# DigitalInput.net
KiCad netlist of a schematic drawn in EAGLE
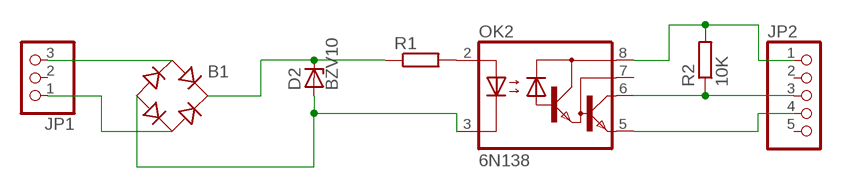
[diagram p0: schematic, sheet 1]

(export (version "E")
  (design (tool "Eeschema 10.0.6"))
  (components
    (comp (ref "B1")
      (value "B-DIL")
      (footprint "eagle-import:B-DIL")
      (libsource (lib "eagle-import") (part "B-DIL"))
    )
    (comp (ref "D2")
      (value "BZV10")
      (footprint "eagle-import:DO34Z7")
      (libsource (lib "eagle-import") (part "BZV10"))
    )
    (comp (ref "JP1")
      (value "PINHD-1X3")
      (footprint "eagle-import:1X03")
      (libsource (lib "eagle-import") (part "PINHD-1X3"))
    )
    (comp (ref "JP2")
      (value "PINHD-1X5")
      (footprint "eagle-import:1X05")
      (libsource (lib "eagle-import") (part "PINHD-1X5"))
    )
    (comp (ref "OK2")
      (value "6N138")
      (footprint "eagle-import:DIL08")
      (fields (field (name "MF") "VISHAY/TELEFUNKEN"))
      (libsource (lib "eagle-import") (part "6N138"))
    )
    (comp (ref "R1")
      (value "R-EU_0204/7")
      (footprint "eagle-import:0204_7")
      (libsource (lib "eagle-import") (part "R-EU_0204/7"))
    )
    (comp (ref "R2")
      (value "10K")
      (footprint "eagle-import:0207_5V")
      (libsource (lib "eagle-import") (part "R-EU_0207/5V"))
    )
  )
  (nets
    (net (code "1") (name "Net-(B1-Pad+)") (class "Default")
      (node (ref "B1") (pin "+") (pinfunction "+_+") (pintype "passive"))
      (node (ref "D2") (pin "C") (pinfunction "C_C") (pintype "passive"))
      (node (ref "R1") (pin "1") (pinfunction "1_1") (pintype "passive"))
    )
    (net (code "2") (name "Net-(B1-PadAC1)") (class "Default")
      (node (ref "B1") (pin "AC1") (pinfunction "AC1_AC1") (pintype "passive"))
      (node (ref "JP1") (pin "3") (pinfunction "3_3") (pintype "passive"))
    )
    (net (code "3") (name "Net-(B1-PadAC2)") (class "Default")
      (node (ref "B1") (pin "AC2") (pinfunction "AC2_AC2") (pintype "passive"))
      (node (ref "JP1") (pin "1") (pinfunction "1_1") (pintype "passive"))
    )
    (net (code "4") (name "Net-(OK2-A)") (class "Default")
      (node (ref "OK2") (pin "2") (pinfunction "A_2") (pintype "passive"))
      (node (ref "R1") (pin "2") (pinfunction "2_2") (pintype "passive"))
    )
    (net (code "5") (name "Net-(OK2-C)") (class "Default")
      (node (ref "B1") (pin "-") (pinfunction "-_-") (pintype "passive"))
      (node (ref "D2") (pin "A") (pinfunction "A_A") (pintype "passive"))
      (node (ref "OK2") (pin "3") (pinfunction "C_3") (pintype "passive"))
    )
    (net (code "6") (name "Net-(OK2-GND)") (class "Default")
      (node (ref "JP2") (pin "4") (pinfunction "4_4") (pintype "passive"))
      (node (ref "OK2") (pin "5") (pinfunction "GND_5") (pintype "passive"))
    )
    (net (code "7") (name "Net-(OK2-VCC)") (class "Default")
      (node (ref "JP2") (pin "1") (pinfunction "1_1") (pintype "passive"))
      (node (ref "OK2") (pin "8") (pinfunction "VCC_8") (pintype "passive"))
      (node (ref "R2") (pin "2") (pinfunction "2_2") (pintype "passive"))
    )
    (net (code "8") (name "Net-(OK2-VO)") (class "Default")
      (node (ref "JP2") (pin "3") (pinfunction "3_3") (pintype "passive"))
      (node (ref "OK2") (pin "6") (pinfunction "VO_6") (pintype "passive"))
      (node (ref "R2") (pin "1") (pinfunction "1_1") (pintype "passive"))
    )
    (net (code "9") (name "unconnected-(JP1-Pad2)") (class "Default")
      (node (ref "JP1") (pin "2") (pinfunction "2_2") (pintype "passive"))
    )
    (net (code "10") (name "unconnected-(JP2-Pad2)") (class "Default")
      (node (ref "JP2") (pin "2") (pinfunction "2_2") (pintype "passive"))
    )
    (net (code "11") (name "unconnected-(JP2-Pad5)") (class "Default")
      (node (ref "JP2") (pin "5") (pinfunction "5_5") (pintype "passive"))
    )
    (net (code "12") (name "unconnected-(OK2-VB-Pad7)") (class "Default")
      (node (ref "OK2") (pin "7") (pinfunction "VB_7") (pintype "passive"))
    )
  )
)
